# BGM111_A.net
KiCad netlist of a schematic drawn in EAGLE
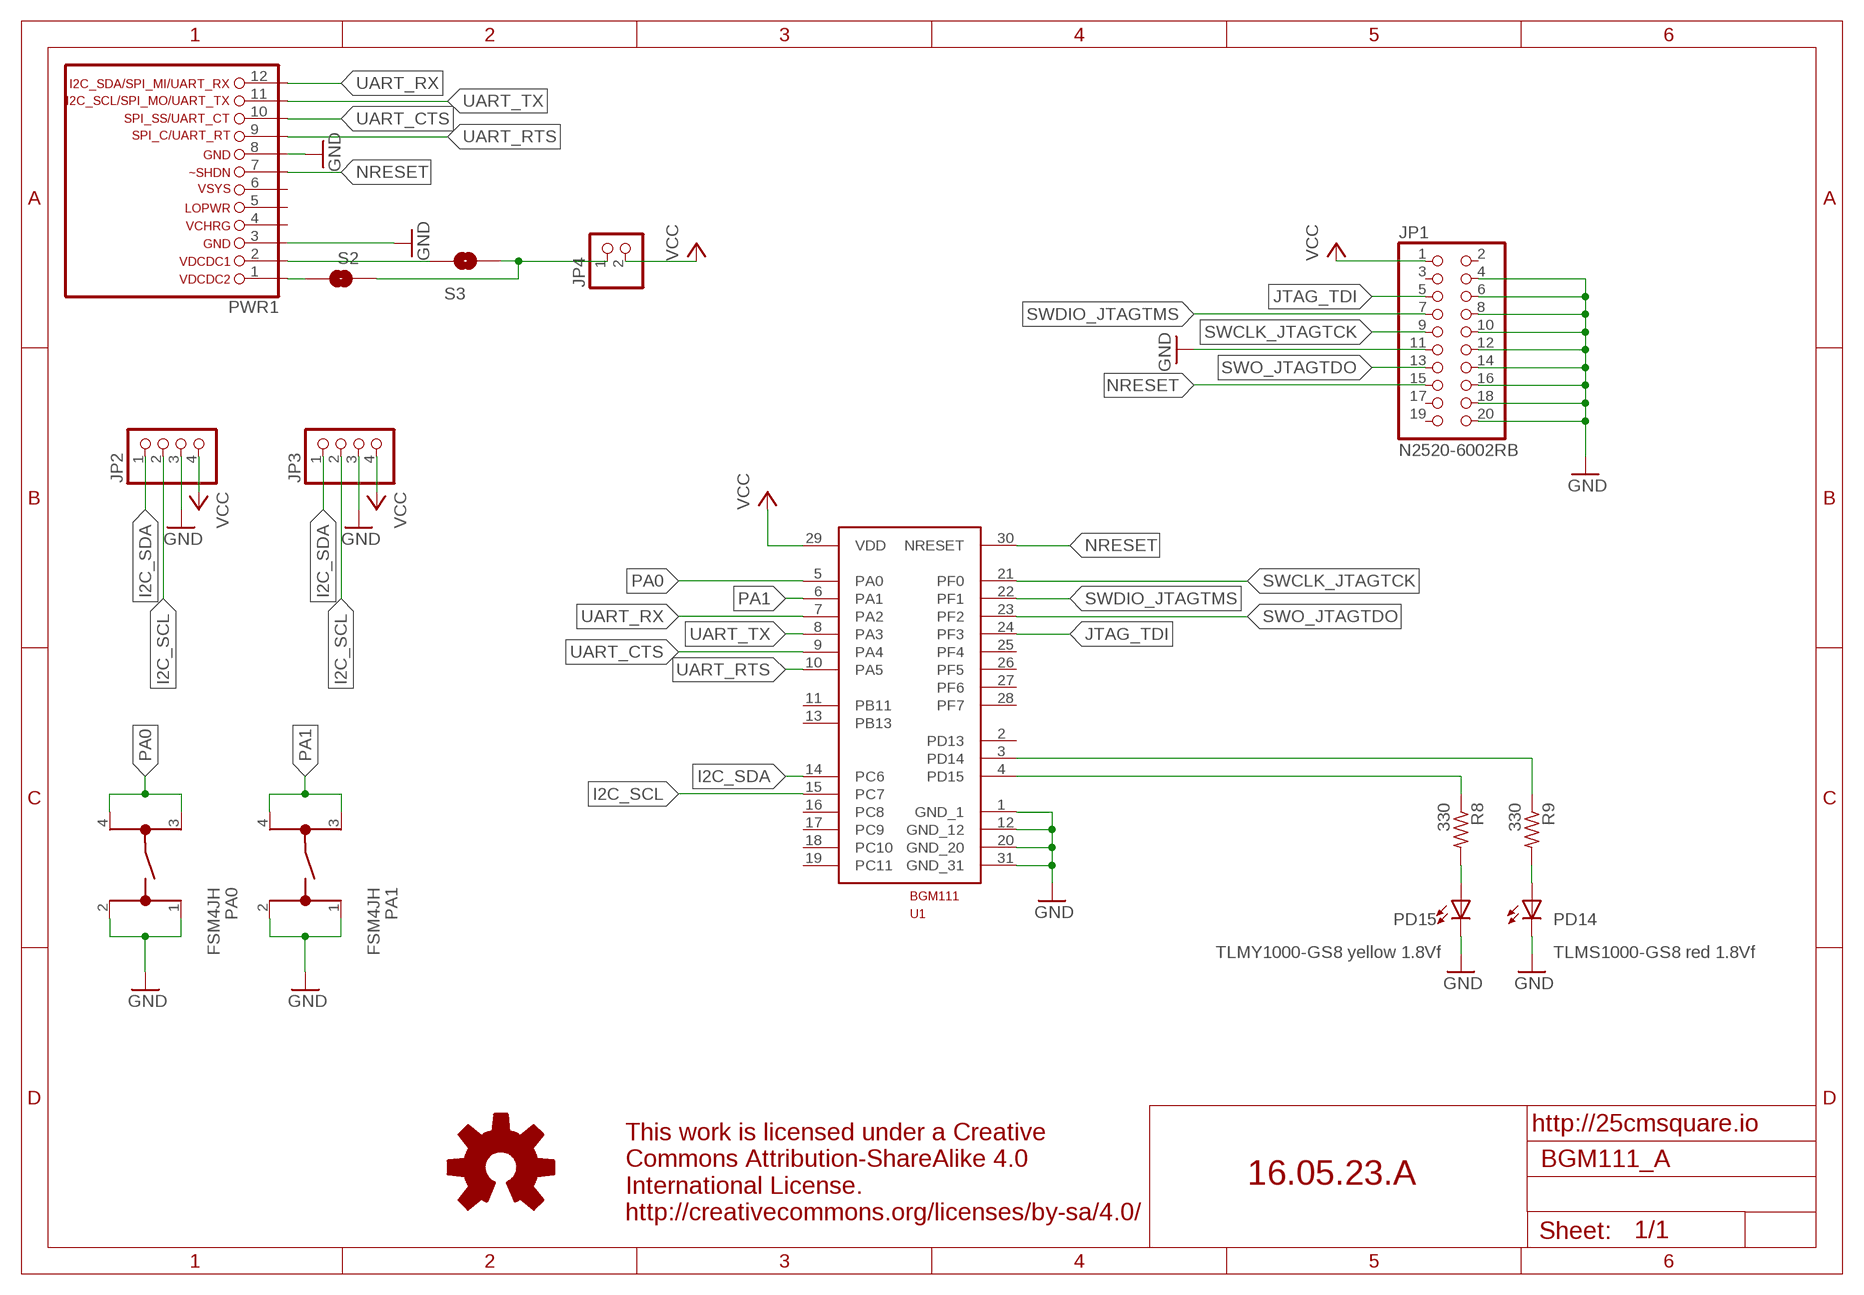
[diagram p0: schematic, sheet 1]

(export (version "E")
  (design (tool "Eeschema 10.0.6"))
  (components
    (comp (ref "JP1")
      (value "N2520-6002RB")
      (footprint "eagle-import:2X10")
      (libsource (lib "eagle-import") (part "PINHD-2X10"))
    )
    (comp (ref "JP2")
      (value "PINHD-1X4")
      (footprint "eagle-import:1X04")
      (libsource (lib "eagle-import") (part "PINHD-1X4"))
    )
    (comp (ref "JP3")
      (value "PINHD-1X4")
      (footprint "eagle-import:1X04")
      (libsource (lib "eagle-import") (part "PINHD-1X4"))
    )
    (comp (ref "JP4")
      (value "PINHD-1X2")
      (footprint "eagle-import:1X02")
      (libsource (lib "eagle-import") (part "PINHD-1X2"))
    )
    (comp (ref "PA0")
      (value "FSM4JH")
      (footprint "eagle-import:FSM4JH")
      (libsource (lib "eagle-import") (part "FSM4JH"))
    )
    (comp (ref "PA1")
      (value "FSM4JH")
      (footprint "eagle-import:FSM4JH")
      (libsource (lib "eagle-import") (part "FSM4JH"))
    )
    (comp (ref "PD14")
      (value "TLMS1000-GS8 red 1.8Vf")
      (footprint "eagle-import:SML0603")
      (libsource (lib "eagle-import") (part "LEDSML0603"))
    )
    (comp (ref "PD15")
      (value "TLMY1000-GS8 yellow 1.8Vf")
      (footprint "eagle-import:SML0603")
      (libsource (lib "eagle-import") (part "LEDSML0603"))
    )
    (comp (ref "PWR1")
      (value "LIWE_12_PIN_PWR")
      (footprint "eagle-import:LIWE_12_PIN")
      (libsource (lib "eagle-import") (part "LIWE_12_PIN_PWR"))
    )
    (comp (ref "R8")
      (value "330")
      (footprint "eagle-import:R0603")
      (libsource (lib "eagle-import") (part "R-US_R0603"))
    )
    (comp (ref "R9")
      (value "330")
      (footprint "eagle-import:R0603")
      (libsource (lib "eagle-import") (part "R-US_R0603"))
    )
    (comp (ref "S2")
      (value "SOLDERJUMPERNC2")
      (footprint "eagle-import:SJ_2S-NOTRACE")
      (libsource (lib "eagle-import") (part "SOLDERJUMPERNC2"))
    )
    (comp (ref "S3")
      (value "SOLDERJUMPERNC2")
      (footprint "eagle-import:SJ_2S-NOTRACE")
      (libsource (lib "eagle-import") (part "SOLDERJUMPERNC2"))
    )
    (comp (ref "U$1")
      (value "OSHW_LOGO")
      (footprint "eagle-import:OSHW")
      (libsource (lib "eagle-import") (part "OSHW_LOGO"))
    )
    (comp (ref "U1")
      (value "BGM111")
      (footprint "eagle-import:BGM111")
      (libsource (lib "eagle-import") (part "BGM111"))
    )
  )
  (nets
    (net (code "1") (name "GND") (class "Default")
      (node (ref "JP1") (pin "10") (pinfunction "10_10") (pintype "passive"))
      (node (ref "JP1") (pin "11") (pinfunction "11_11") (pintype "passive"))
      (node (ref "JP1") (pin "12") (pinfunction "12_12") (pintype "passive"))
      (node (ref "JP1") (pin "14") (pinfunction "14_14") (pintype "passive"))
      (node (ref "JP1") (pin "16") (pinfunction "16_16") (pintype "passive"))
      (node (ref "JP1") (pin "18") (pinfunction "18_18") (pintype "passive"))
      (node (ref "JP1") (pin "20") (pinfunction "20_20") (pintype "passive"))
      (node (ref "JP1") (pin "4") (pinfunction "4_4") (pintype "passive"))
      (node (ref "JP1") (pin "6") (pinfunction "6_6") (pintype "passive"))
      (node (ref "JP1") (pin "8") (pinfunction "8_8") (pintype "passive"))
      (node (ref "JP2") (pin "3") (pinfunction "3_3") (pintype "passive"))
      (node (ref "JP3") (pin "3") (pinfunction "3_3") (pintype "passive"))
      (node (ref "PA0") (pin "1") (pinfunction "1_1") (pintype "passive"))
      (node (ref "PA0") (pin "2") (pinfunction "2_2") (pintype "passive"))
      (node (ref "PA1") (pin "1") (pinfunction "1_1") (pintype "passive"))
      (node (ref "PA1") (pin "2") (pinfunction "2_2") (pintype "passive"))
      (node (ref "PD14") (pin "C") (pinfunction "C_C") (pintype "passive"))
      (node (ref "PD15") (pin "C") (pinfunction "C_C") (pintype "passive"))
      (node (ref "PWR1") (pin "3") (pinfunction "3_3") (pintype "passive"))
      (node (ref "PWR1") (pin "8") (pinfunction "8_8") (pintype "passive"))
      (node (ref "U1") (pin "1") (pinfunction "GND_1_1") (pintype "power_in"))
      (node (ref "U1") (pin "12") (pinfunction "GND_12_12") (pintype "power_in"))
      (node (ref "U1") (pin "20") (pinfunction "GND_20_20") (pintype "power_in"))
      (node (ref "U1") (pin "31") (pinfunction "GND_31_31") (pintype "power_in"))
    )
    (net (code "2") (name "I2C_SCL") (class "Default")
      (node (ref "JP2") (pin "2") (pinfunction "2_2") (pintype "passive"))
      (node (ref "JP3") (pin "2") (pinfunction "2_2") (pintype "passive"))
      (node (ref "U1") (pin "15") (pinfunction "PC7_15") (pintype "bidirectional"))
    )
    (net (code "3") (name "I2C_SDA") (class "Default")
      (node (ref "JP2") (pin "1") (pinfunction "1_1") (pintype "passive"))
      (node (ref "JP3") (pin "1") (pinfunction "1_1") (pintype "passive"))
      (node (ref "U1") (pin "14") (pinfunction "PC6_14") (pintype "bidirectional"))
    )
    (net (code "4") (name "JTAG_TDI") (class "Default")
      (node (ref "JP1") (pin "5") (pinfunction "5_5") (pintype "passive"))
      (node (ref "U1") (pin "24") (pinfunction "PF3_24") (pintype "bidirectional"))
    )
    (net (code "5") (name "NRESET") (class "Default")
      (node (ref "JP1") (pin "15") (pinfunction "15_15") (pintype "passive"))
      (node (ref "PWR1") (pin "7") (pinfunction "7_7") (pintype "passive"))
      (node (ref "U1") (pin "30") (pinfunction "NRESET_30") (pintype "bidirectional"))
    )
    (net (code "6") (name "Net-(JP4-Pad1)") (class "Default")
      (node (ref "JP4") (pin "1") (pinfunction "1_1") (pintype "passive"))
      (node (ref "S2") (pin "2") (pinfunction "2_2") (pintype "passive"))
      (node (ref "S3") (pin "2") (pinfunction "2_2") (pintype "passive"))
    )
    (net (code "7") (name "Net-(PD14-PadA)") (class "Default")
      (node (ref "PD14") (pin "A") (pinfunction "A_A") (pintype "passive"))
      (node (ref "R9") (pin "2") (pinfunction "2_2") (pintype "passive"))
    )
    (net (code "8") (name "Net-(PD15-PadA)") (class "Default")
      (node (ref "PD15") (pin "A") (pinfunction "A_A") (pintype "passive"))
      (node (ref "R8") (pin "2") (pinfunction "2_2") (pintype "passive"))
    )
    (net (code "9") (name "Net-(PWR1-Pad1)") (class "Default")
      (node (ref "PWR1") (pin "1") (pinfunction "1_1") (pintype "passive"))
      (node (ref "S2") (pin "1") (pinfunction "1_1") (pintype "passive"))
    )
    (net (code "10") (name "Net-(PWR1-Pad2)") (class "Default")
      (node (ref "PWR1") (pin "2") (pinfunction "2_2") (pintype "passive"))
      (node (ref "S3") (pin "1") (pinfunction "1_1") (pintype "passive"))
    )
    (net (code "11") (name "Net-(U1-PD14)") (class "Default")
      (node (ref "R9") (pin "1") (pinfunction "1_1") (pintype "passive"))
      (node (ref "U1") (pin "3") (pinfunction "PD14_3") (pintype "bidirectional"))
    )
    (net (code "12") (name "Net-(U1-PD15)") (class "Default")
      (node (ref "R8") (pin "1") (pinfunction "1_1") (pintype "passive"))
      (node (ref "U1") (pin "4") (pinfunction "PD15_4") (pintype "bidirectional"))
    )
    (net (code "13") (name "PA0") (class "Default")
      (node (ref "PA0") (pin "3") (pinfunction "3_3") (pintype "passive"))
      (node (ref "PA0") (pin "4") (pinfunction "4_4") (pintype "passive"))
      (node (ref "U1") (pin "5") (pinfunction "PA0_5") (pintype "bidirectional"))
    )
    (net (code "14") (name "PA1") (class "Default")
      (node (ref "PA1") (pin "3") (pinfunction "3_3") (pintype "passive"))
      (node (ref "PA1") (pin "4") (pinfunction "4_4") (pintype "passive"))
      (node (ref "U1") (pin "6") (pinfunction "PA1_6") (pintype "bidirectional"))
    )
    (net (code "15") (name "SWCLK_JTAGTCK") (class "Default")
      (node (ref "JP1") (pin "9") (pinfunction "9_9") (pintype "passive"))
      (node (ref "U1") (pin "21") (pinfunction "PF0_21") (pintype "bidirectional"))
    )
    (net (code "16") (name "SWDIO_JTAGTMS") (class "Default")
      (node (ref "JP1") (pin "7") (pinfunction "7_7") (pintype "passive"))
      (node (ref "U1") (pin "22") (pinfunction "PF1_22") (pintype "bidirectional"))
    )
    (net (code "17") (name "SWO_JTAGTDO") (class "Default")
      (node (ref "JP1") (pin "13") (pinfunction "13_13") (pintype "passive"))
      (node (ref "U1") (pin "23") (pinfunction "PF2_23") (pintype "bidirectional"))
    )
    (net (code "18") (name "UART_CTS") (class "Default")
      (node (ref "PWR1") (pin "10") (pinfunction "10_10") (pintype "passive"))
      (node (ref "U1") (pin "9") (pinfunction "PA4_9") (pintype "bidirectional"))
    )
    (net (code "19") (name "UART_RTS") (class "Default")
      (node (ref "PWR1") (pin "9") (pinfunction "9_9") (pintype "passive"))
      (node (ref "U1") (pin "10") (pinfunction "PA5_10") (pintype "bidirectional"))
    )
    (net (code "20") (name "UART_RX") (class "Default")
      (node (ref "PWR1") (pin "12") (pinfunction "12_12") (pintype "passive"))
      (node (ref "U1") (pin "7") (pinfunction "PA2_7") (pintype "bidirectional"))
    )
    (net (code "21") (name "UART_TX") (class "Default")
      (node (ref "PWR1") (pin "11") (pinfunction "11_11") (pintype "passive"))
      (node (ref "U1") (pin "8") (pinfunction "PA3_8") (pintype "bidirectional"))
    )
    (net (code "22") (name "VCC") (class "Default")
      (node (ref "JP1") (pin "1") (pinfunction "1_1") (pintype "passive"))
      (node (ref "JP2") (pin "4") (pinfunction "4_4") (pintype "passive"))
      (node (ref "JP3") (pin "4") (pinfunction "4_4") (pintype "passive"))
      (node (ref "JP4") (pin "2") (pinfunction "2_2") (pintype "passive"))
      (node (ref "U1") (pin "29") (pinfunction "VDD_29") (pintype "power_in"))
    )
    (net (code "23") (name "unconnected-(JP1-Pad2)") (class "Default")
      (node (ref "JP1") (pin "2") (pinfunction "2_2") (pintype "passive"))
    )
    (net (code "24") (name "unconnected-(JP1-Pad3)") (class "Default")
      (node (ref "JP1") (pin "3") (pinfunction "3_3") (pintype "passive"))
    )
    (net (code "25") (name "unconnected-(JP1-Pad17)") (class "Default")
      (node (ref "JP1") (pin "17") (pinfunction "17_17") (pintype "passive"))
    )
    (net (code "26") (name "unconnected-(JP1-Pad19)") (class "Default")
      (node (ref "JP1") (pin "19") (pinfunction "19_19") (pintype "passive"))
    )
    (net (code "27") (name "unconnected-(PWR1-Pad4)") (class "Default")
      (node (ref "PWR1") (pin "4") (pinfunction "4_4") (pintype "passive"))
    )
    (net (code "28") (name "unconnected-(PWR1-Pad5)") (class "Default")
      (node (ref "PWR1") (pin "5") (pinfunction "5_5") (pintype "passive"))
    )
    (net (code "29") (name "unconnected-(PWR1-Pad6)") (class "Default")
      (node (ref "PWR1") (pin "6") (pinfunction "6_6") (pintype "passive"))
    )
    (net (code "30") (name "unconnected-(U1-PB11-Pad11)") (class "Default")
      (node (ref "U1") (pin "11") (pinfunction "PB11_11") (pintype "bidirectional"))
    )
    (net (code "31") (name "unconnected-(U1-PB13-Pad13)") (class "Default")
      (node (ref "U1") (pin "13") (pinfunction "PB13_13") (pintype "bidirectional"))
    )
    (net (code "32") (name "unconnected-(U1-PC8-Pad16)") (class "Default")
      (node (ref "U1") (pin "16") (pinfunction "PC8_16") (pintype "bidirectional"))
    )
    (net (code "33") (name "unconnected-(U1-PC9-Pad17)") (class "Default")
      (node (ref "U1") (pin "17") (pinfunction "PC9_17") (pintype "bidirectional"))
    )
    (net (code "34") (name "unconnected-(U1-PC10-Pad18)") (class "Default")
      (node (ref "U1") (pin "18") (pinfunction "PC10_18") (pintype "bidirectional"))
    )
    (net (code "35") (name "unconnected-(U1-PC11-Pad19)") (class "Default")
      (node (ref "U1") (pin "19") (pinfunction "PC11_19") (pintype "bidirectional"))
    )
    (net (code "36") (name "unconnected-(U1-PD13-Pad2)") (class "Default")
      (node (ref "U1") (pin "2") (pinfunction "PD13_2") (pintype "bidirectional"))
    )
    (net (code "37") (name "unconnected-(U1-PF4-Pad25)") (class "Default")
      (node (ref "U1") (pin "25") (pinfunction "PF4_25") (pintype "bidirectional"))
    )
    (net (code "38") (name "unconnected-(U1-PF5-Pad26)") (class "Default")
      (node (ref "U1") (pin "26") (pinfunction "PF5_26") (pintype "bidirectional"))
    )
    (net (code "39") (name "unconnected-(U1-PF6-Pad27)") (class "Default")
      (node (ref "U1") (pin "27") (pinfunction "PF6_27") (pintype "bidirectional"))
    )
    (net (code "40") (name "unconnected-(U1-PF7-Pad28)") (class "Default")
      (node (ref "U1") (pin "28") (pinfunction "PF7_28") (pintype "bidirectional"))
    )
  )
)
